# SCH_BalanceCar_2022-06-02.net
KiCad netlist of a schematic drawn in EasyEDA
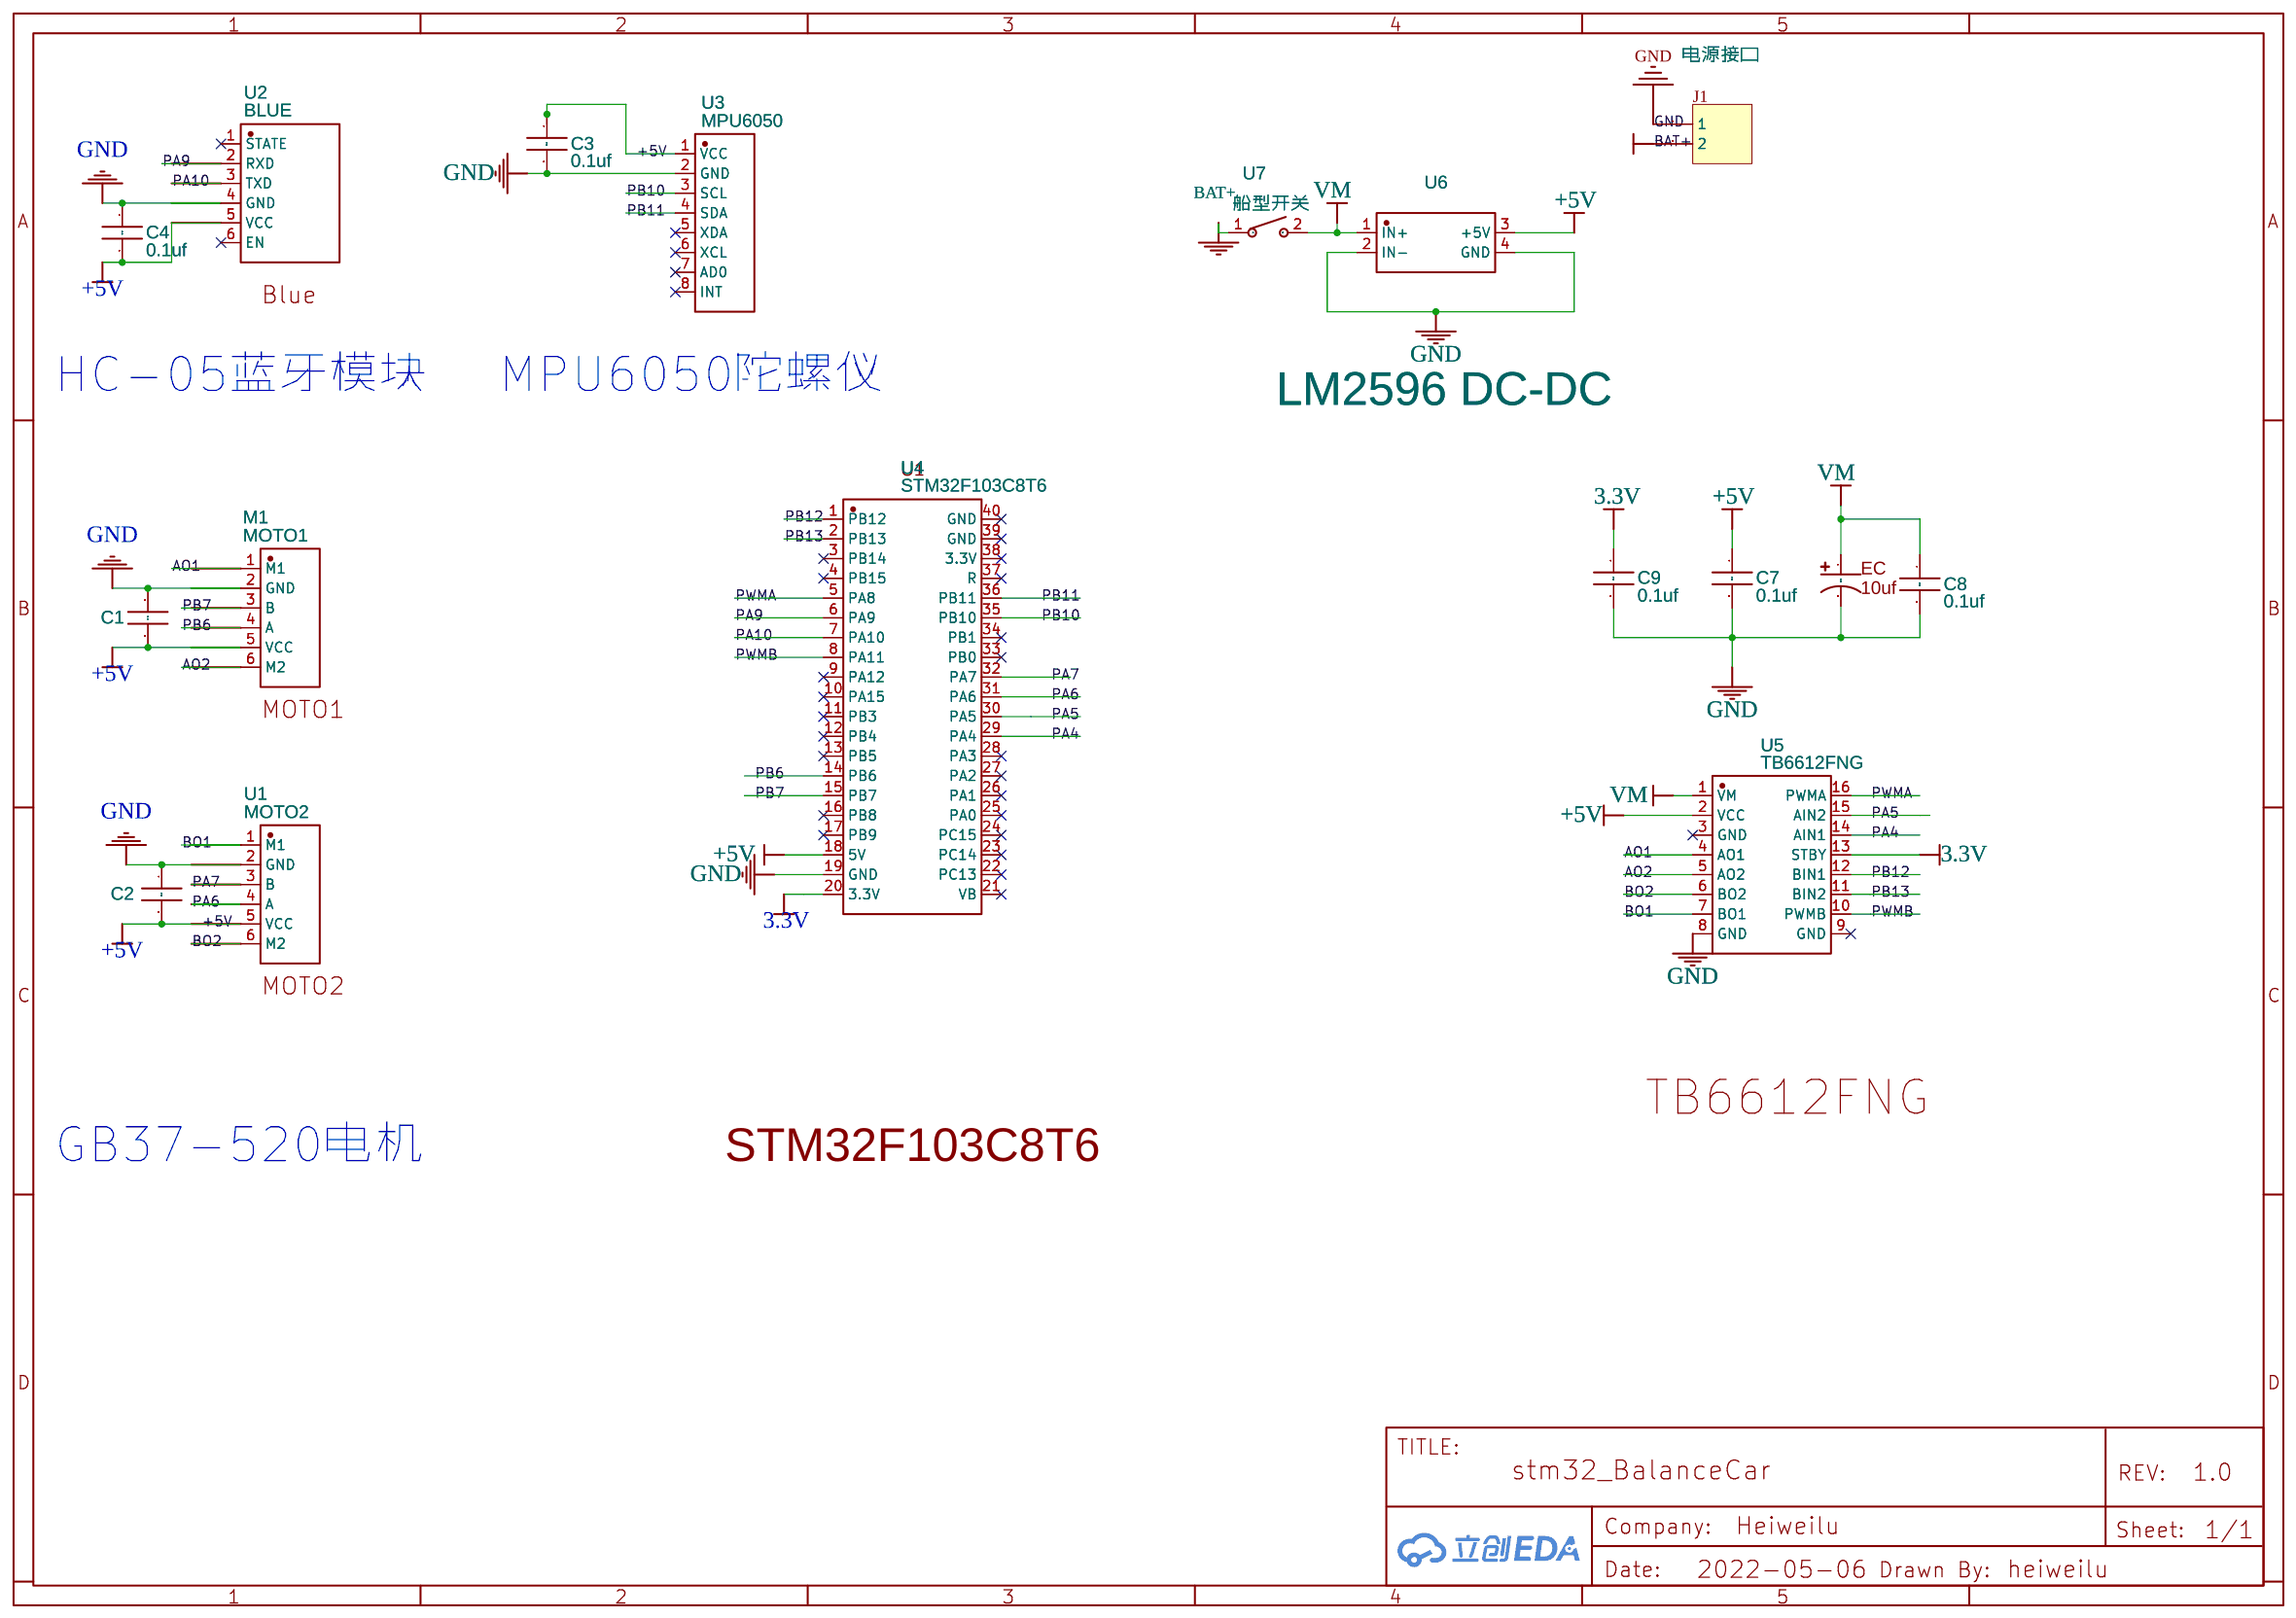
[diagram p0: schematic sheet]

(export (version "E")
  (design (tool "Eeschema 10.0.6"))
  (components
    (comp (ref "C1")
      (value "0.1uf")
      (fields
        (field (name "BOM_Manufacturer Part") "0.1uF 50V 4*5 Black high frequency")
        (field (name "BOM_Supplier Part") "C45093")
      )
      (libsource (lib "") (part "MLCC5.08-A"))
    )
    (comp (ref "C2")
      (value "0.1uf")
      (fields
        (field (name "BOM_Manufacturer Part") "0.1uF 50V 4*5 Black high frequency")
        (field (name "BOM_Supplier Part") "C45093")
      )
      (libsource (lib "") (part "MLCC5.08-A"))
    )
    (comp (ref "C3") (value "0.1uf") (libsource (lib "") (part "0.1uf退耦电容")))
    (comp (ref "C4") (value "0.1uf") (libsource (lib "") (part "0.1uf退耦电容")))
    (comp (ref "C7") (value "0.1uf") (libsource (lib "") (part "0.1uf")))
    (comp (ref "C8") (value "0.1uf") (libsource (lib "") (part "0.1uf退耦电容")))
    (comp (ref "C9") (value "0.1uf") (libsource (lib "") (part "0.1uf")))
    (comp (ref "C12") (value "10uf") (libsource (lib "") (part "10uf")))
    (comp (ref "J")
      (value "电源接口")
      (fields
        (field (name "BOM_Manufacturer Part") "WJ301V-5.0-2P")
        (field (name "BOM_Supplier Part") "C8475")
      )
      (libsource (lib "") (part "电源接口"))
    )
    (comp (ref "M1")
      (value "MOTO1")
      (fields (field (name "BOM_Manufacturer Part") "XH-6AW") (field (name "BOM_Supplier Part") "C8876"))
      (libsource (lib "") (part "MOTO1"))
    )
    (comp (ref "U1")
      (value "MOTO2")
      (fields (field (name "BOM_Manufacturer Part") "XH-6AW") (field (name "BOM_Supplier Part") "C8876"))
      (libsource (lib "") (part "MOTO2"))
    )
    (comp (ref "U2") (value "BLUE") (libsource (lib "") (part "BLUE")))
    (comp (ref "U3") (value "MPU6050") (libsource (lib "") (part "MPU6050")))
    (comp (ref "U4") (value "STM32F103C8T6") (libsource (lib "") (part "STM32F103C8T6")))
    (comp (ref "U5") (value "TB6612FNG") (libsource (lib "") (part "TB6612FNG")))
    (comp (ref "U6") (value "LM2596 DC-DC") (libsource (lib "") (part "LM2596 DC-DC")))
    (comp (ref "U7") (value "船型开关") (libsource (lib "") (part "船型开关")))
  )
  (nets
    (net (code "1") (name "+5V") (class "Default")
      (node (ref "C1") (pin "2") (pinfunction "2_2") (pintype "unspecified"))
      (node (ref "C2") (pin "2") (pinfunction "2_2") (pintype "unspecified"))
      (node (ref "C3") (pin "1") (pinfunction "1_1") (pintype "unspecified"))
      (node (ref "C4") (pin "2") (pinfunction "2_2") (pintype "unspecified"))
      (node (ref "C7") (pin "1") (pinfunction "1_1") (pintype "unspecified"))
      (node (ref "M1") (pin "5") (pinfunction "VCC_5") (pintype "unspecified"))
      (node (ref "U1") (pin "5") (pinfunction "VCC_5") (pintype "unspecified"))
      (node (ref "U2") (pin "5") (pinfunction "VCC_5") (pintype "unspecified"))
      (node (ref "U3") (pin "1") (pinfunction "VCC_1") (pintype "unspecified"))
      (node (ref "U4") (pin "18") (pinfunction "5V_18") (pintype "unspecified"))
      (node (ref "U5") (pin "2") (pinfunction "VCC_2") (pintype "unspecified"))
      (node (ref "U6") (pin "3") (pinfunction "+5V_3") (pintype "unspecified"))
    )
    (net (code "2") (name "/AO1") (class "Default")
      (node (ref "M1") (pin "1") (pinfunction "M1_1") (pintype "unspecified"))
      (node (ref "U5") (pin "4") (pinfunction "AO1_4") (pintype "unspecified"))
    )
    (net (code "3") (name "/AO2") (class "Default")
      (node (ref "M1") (pin "6") (pinfunction "M2_6") (pintype "unspecified"))
      (node (ref "U5") (pin "5") (pinfunction "AO2_5") (pintype "unspecified"))
    )
    (net (code "4") (name "/BO1") (class "Default")
      (node (ref "U1") (pin "1") (pinfunction "M1_1") (pintype "unspecified"))
      (node (ref "U5") (pin "7") (pinfunction "BO1_7") (pintype "unspecified"))
    )
    (net (code "5") (name "/BO2") (class "Default")
      (node (ref "U1") (pin "6") (pinfunction "M2_6") (pintype "unspecified"))
      (node (ref "U5") (pin "6") (pinfunction "BO2_6") (pintype "unspecified"))
    )
    (net (code "6") (name "/PA4") (class "Default")
      (node (ref "U4") (pin "29") (pinfunction "PA4_29") (pintype "unspecified"))
      (node (ref "U5") (pin "14") (pinfunction "AIN1_14") (pintype "unspecified"))
    )
    (net (code "7") (name "/PA5") (class "Default")
      (node (ref "U4") (pin "30") (pinfunction "PA5_30") (pintype "unspecified"))
      (node (ref "U5") (pin "15") (pinfunction "AIN2_15") (pintype "unspecified"))
    )
    (net (code "8") (name "/PA6") (class "Default")
      (node (ref "U1") (pin "4") (pinfunction "A_4") (pintype "unspecified"))
      (node (ref "U4") (pin "31") (pinfunction "PA6_31") (pintype "unspecified"))
    )
    (net (code "9") (name "/PA7") (class "Default")
      (node (ref "U1") (pin "3") (pinfunction "B_3") (pintype "unspecified"))
      (node (ref "U4") (pin "32") (pinfunction "PA7_32") (pintype "unspecified"))
    )
    (net (code "10") (name "/PA9") (class "Default")
      (node (ref "U2") (pin "2") (pinfunction "RXD_2") (pintype "unspecified"))
      (node (ref "U4") (pin "6") (pinfunction "PA9_6") (pintype "unspecified"))
    )
    (net (code "11") (name "/PA10") (class "Default")
      (node (ref "U2") (pin "3") (pinfunction "TXD_3") (pintype "unspecified"))
      (node (ref "U4") (pin "7") (pinfunction "PA10_7") (pintype "unspecified"))
    )
    (net (code "12") (name "/PB6") (class "Default")
      (node (ref "M1") (pin "4") (pinfunction "A_4") (pintype "unspecified"))
      (node (ref "U4") (pin "14") (pinfunction "PB6_14") (pintype "unspecified"))
    )
    (net (code "13") (name "/PB7") (class "Default")
      (node (ref "M1") (pin "3") (pinfunction "B_3") (pintype "unspecified"))
      (node (ref "U4") (pin "15") (pinfunction "PB7_15") (pintype "unspecified"))
    )
    (net (code "14") (name "/PB10") (class "Default")
      (node (ref "U3") (pin "3") (pinfunction "SCL_3") (pintype "unspecified"))
      (node (ref "U4") (pin "35") (pinfunction "PB10_35") (pintype "unspecified"))
    )
    (net (code "15") (name "/PB11") (class "Default")
      (node (ref "U3") (pin "4") (pinfunction "SDA_4") (pintype "unspecified"))
      (node (ref "U4") (pin "36") (pinfunction "PB11_36") (pintype "unspecified"))
    )
    (net (code "16") (name "/PB12") (class "Default")
      (node (ref "U4") (pin "1") (pinfunction "PB12_1") (pintype "unspecified"))
      (node (ref "U5") (pin "12") (pinfunction "BIN1_12") (pintype "unspecified"))
    )
    (net (code "17") (name "/PB13") (class "Default")
      (node (ref "U4") (pin "2") (pinfunction "PB13_2") (pintype "unspecified"))
      (node (ref "U5") (pin "11") (pinfunction "BIN2_11") (pintype "unspecified"))
    )
    (net (code "18") (name "/PWMA") (class "Default")
      (node (ref "U4") (pin "5") (pinfunction "PA8_5") (pintype "unspecified"))
      (node (ref "U5") (pin "16") (pinfunction "PWMA_16") (pintype "unspecified"))
    )
    (net (code "19") (name "/PWMB") (class "Default")
      (node (ref "U4") (pin "8") (pinfunction "PA11_8") (pintype "unspecified"))
      (node (ref "U5") (pin "10") (pinfunction "PWMB_10") (pintype "unspecified"))
    )
    (net (code "20") (name "3.3V") (class "Default")
      (node (ref "C9") (pin "1") (pinfunction "1_1") (pintype "unspecified"))
      (node (ref "U4") (pin "20") (pinfunction "3.3V_20") (pintype "unspecified"))
      (node (ref "U5") (pin "13") (pinfunction "STBY_13") (pintype "unspecified"))
    )
    (net (code "21") (name "BAT+") (class "Default")
      (node (ref "J") (pin "2") (pinfunction "2_2") (pintype "unspecified"))
      (node (ref "U7") (pin "1") (pinfunction "1_1") (pintype "unspecified"))
    )
    (net (code "22") (name "GND") (class "Default")
      (node (ref "C1") (pin "1") (pinfunction "1_1") (pintype "unspecified"))
      (node (ref "C12") (pin "2") (pinfunction "2_2") (pintype "unspecified"))
      (node (ref "C2") (pin "1") (pinfunction "1_1") (pintype "unspecified"))
      (node (ref "C3") (pin "2") (pinfunction "2_2") (pintype "unspecified"))
      (node (ref "C4") (pin "1") (pinfunction "1_1") (pintype "unspecified"))
      (node (ref "C7") (pin "2") (pinfunction "2_2") (pintype "unspecified"))
      (node (ref "C8") (pin "2") (pinfunction "2_2") (pintype "unspecified"))
      (node (ref "C9") (pin "2") (pinfunction "2_2") (pintype "unspecified"))
      (node (ref "J") (pin "1") (pinfunction "1_1") (pintype "unspecified"))
      (node (ref "M1") (pin "2") (pinfunction "GND_2") (pintype "unspecified"))
      (node (ref "U1") (pin "2") (pinfunction "GND_2") (pintype "unspecified"))
      (node (ref "U2") (pin "4") (pinfunction "GND_4") (pintype "unspecified"))
      (node (ref "U3") (pin "2") (pinfunction "GND_2") (pintype "unspecified"))
      (node (ref "U4") (pin "19") (pinfunction "GND_19") (pintype "unspecified"))
      (node (ref "U5") (pin "8") (pinfunction "GND_8") (pintype "unspecified"))
      (node (ref "U6") (pin "2") (pinfunction "IN-_2") (pintype "unspecified"))
      (node (ref "U6") (pin "4") (pinfunction "GND_4") (pintype "unspecified"))
    )
    (net (code "23") (name "VM") (class "Default")
      (node (ref "C12") (pin "1") (pinfunction "1_1") (pintype "unspecified"))
      (node (ref "C8") (pin "1") (pinfunction "1_1") (pintype "unspecified"))
      (node (ref "U5") (pin "1") (pinfunction "VM_1") (pintype "unspecified"))
      (node (ref "U6") (pin "1") (pinfunction "IN+_1") (pintype "unspecified"))
      (node (ref "U7") (pin "2") (pinfunction "2_2") (pintype "unspecified"))
    )
    (net (code "24") (name "unconnected-(U2-EN-Pad6)") (class "Default")
      (node (ref "U2") (pin "6") (pinfunction "EN_6") (pintype "unspecified+no_connect"))
    )
    (net (code "25") (name "unconnected-(U2-STATE-Pad1)") (class "Default")
      (node (ref "U2") (pin "1") (pinfunction "STATE_1") (pintype "unspecified+no_connect"))
    )
    (net (code "26") (name "unconnected-(U3-AD0-Pad7)") (class "Default")
      (node (ref "U3") (pin "7") (pinfunction "AD0_7") (pintype "unspecified+no_connect"))
    )
    (net (code "27") (name "unconnected-(U3-INT-Pad8)") (class "Default")
      (node (ref "U3") (pin "8") (pinfunction "INT_8") (pintype "unspecified+no_connect"))
    )
    (net (code "28") (name "unconnected-(U3-XCL-Pad6)") (class "Default")
      (node (ref "U3") (pin "6") (pinfunction "XCL_6") (pintype "unspecified+no_connect"))
    )
    (net (code "29") (name "unconnected-(U3-XDA-Pad5)") (class "Default")
      (node (ref "U3") (pin "5") (pinfunction "XDA_5") (pintype "unspecified+no_connect"))
    )
    (net (code "30") (name "unconnected-(U4-3.3V-Pad38)") (class "Default")
      (node (ref "U4") (pin "38") (pinfunction "3.3V_38") (pintype "unspecified+no_connect"))
    )
    (net (code "31") (name "unconnected-(U4-GND-Pad39)") (class "Default")
      (node (ref "U4") (pin "39") (pinfunction "GND_39") (pintype "unspecified+no_connect"))
    )
    (net (code "32") (name "unconnected-(U4-GND-Pad40)") (class "Default")
      (node (ref "U4") (pin "40") (pinfunction "GND_40") (pintype "unspecified+no_connect"))
    )
    (net (code "33") (name "unconnected-(U4-PA0-Pad25)") (class "Default")
      (node (ref "U4") (pin "25") (pinfunction "PA0_25") (pintype "unspecified+no_connect"))
    )
    (net (code "34") (name "unconnected-(U4-PA1-Pad26)") (class "Default")
      (node (ref "U4") (pin "26") (pinfunction "PA1_26") (pintype "unspecified+no_connect"))
    )
    (net (code "35") (name "unconnected-(U4-PA2-Pad27)") (class "Default")
      (node (ref "U4") (pin "27") (pinfunction "PA2_27") (pintype "unspecified+no_connect"))
    )
    (net (code "36") (name "unconnected-(U4-PA3-Pad28)") (class "Default")
      (node (ref "U4") (pin "28") (pinfunction "PA3_28") (pintype "unspecified+no_connect"))
    )
    (net (code "37") (name "unconnected-(U4-PA12-Pad9)") (class "Default")
      (node (ref "U4") (pin "9") (pinfunction "PA12_9") (pintype "unspecified+no_connect"))
    )
    (net (code "38") (name "unconnected-(U4-PA15-Pad10)") (class "Default")
      (node (ref "U4") (pin "10") (pinfunction "PA15_10") (pintype "unspecified+no_connect"))
    )
    (net (code "39") (name "unconnected-(U4-PB0-Pad33)") (class "Default")
      (node (ref "U4") (pin "33") (pinfunction "PB0_33") (pintype "unspecified+no_connect"))
    )
    (net (code "40") (name "unconnected-(U4-PB1-Pad34)") (class "Default")
      (node (ref "U4") (pin "34") (pinfunction "PB1_34") (pintype "unspecified+no_connect"))
    )
    (net (code "41") (name "unconnected-(U4-PB3-Pad11)") (class "Default")
      (node (ref "U4") (pin "11") (pinfunction "PB3_11") (pintype "unspecified+no_connect"))
    )
    (net (code "42") (name "unconnected-(U4-PB4-Pad12)") (class "Default")
      (node (ref "U4") (pin "12") (pinfunction "PB4_12") (pintype "unspecified+no_connect"))
    )
    (net (code "43") (name "unconnected-(U4-PB5-Pad13)") (class "Default")
      (node (ref "U4") (pin "13") (pinfunction "PB5_13") (pintype "unspecified+no_connect"))
    )
    (net (code "44") (name "unconnected-(U4-PB8-Pad16)") (class "Default")
      (node (ref "U4") (pin "16") (pinfunction "PB8_16") (pintype "unspecified+no_connect"))
    )
    (net (code "45") (name "unconnected-(U4-PB9-Pad17)") (class "Default")
      (node (ref "U4") (pin "17") (pinfunction "PB9_17") (pintype "unspecified+no_connect"))
    )
    (net (code "46") (name "unconnected-(U4-PB14-Pad3)") (class "Default")
      (node (ref "U4") (pin "3") (pinfunction "PB14_3") (pintype "unspecified+no_connect"))
    )
    (net (code "47") (name "unconnected-(U4-PB15-Pad4)") (class "Default")
      (node (ref "U4") (pin "4") (pinfunction "PB15_4") (pintype "unspecified+no_connect"))
    )
    (net (code "48") (name "unconnected-(U4-PC13-Pad22)") (class "Default")
      (node (ref "U4") (pin "22") (pinfunction "PC13_22") (pintype "unspecified+no_connect"))
    )
    (net (code "49") (name "unconnected-(U4-PC14-Pad23)") (class "Default")
      (node (ref "U4") (pin "23") (pinfunction "PC14_23") (pintype "unspecified+no_connect"))
    )
    (net (code "50") (name "unconnected-(U4-PC15-Pad24)") (class "Default")
      (node (ref "U4") (pin "24") (pinfunction "PC15_24") (pintype "unspecified+no_connect"))
    )
    (net (code "51") (name "unconnected-(U4-R-Pad37)") (class "Default")
      (node (ref "U4") (pin "37") (pinfunction "R_37") (pintype "unspecified+no_connect"))
    )
    (net (code "52") (name "unconnected-(U4-VB-Pad21)") (class "Default")
      (node (ref "U4") (pin "21") (pinfunction "VB_21") (pintype "unspecified+no_connect"))
    )
    (net (code "53") (name "unconnected-(U5-GND-Pad3)") (class "Default")
      (node (ref "U5") (pin "3") (pinfunction "GND_3") (pintype "unspecified+no_connect"))
    )
    (net (code "54") (name "unconnected-(U5-GND-Pad9)") (class "Default")
      (node (ref "U5") (pin "9") (pinfunction "GND_9") (pintype "unspecified+no_connect"))
    )
  )
)
